# al_1S_charger.net
KiCad netlist of a schematic drawn in EAGLE
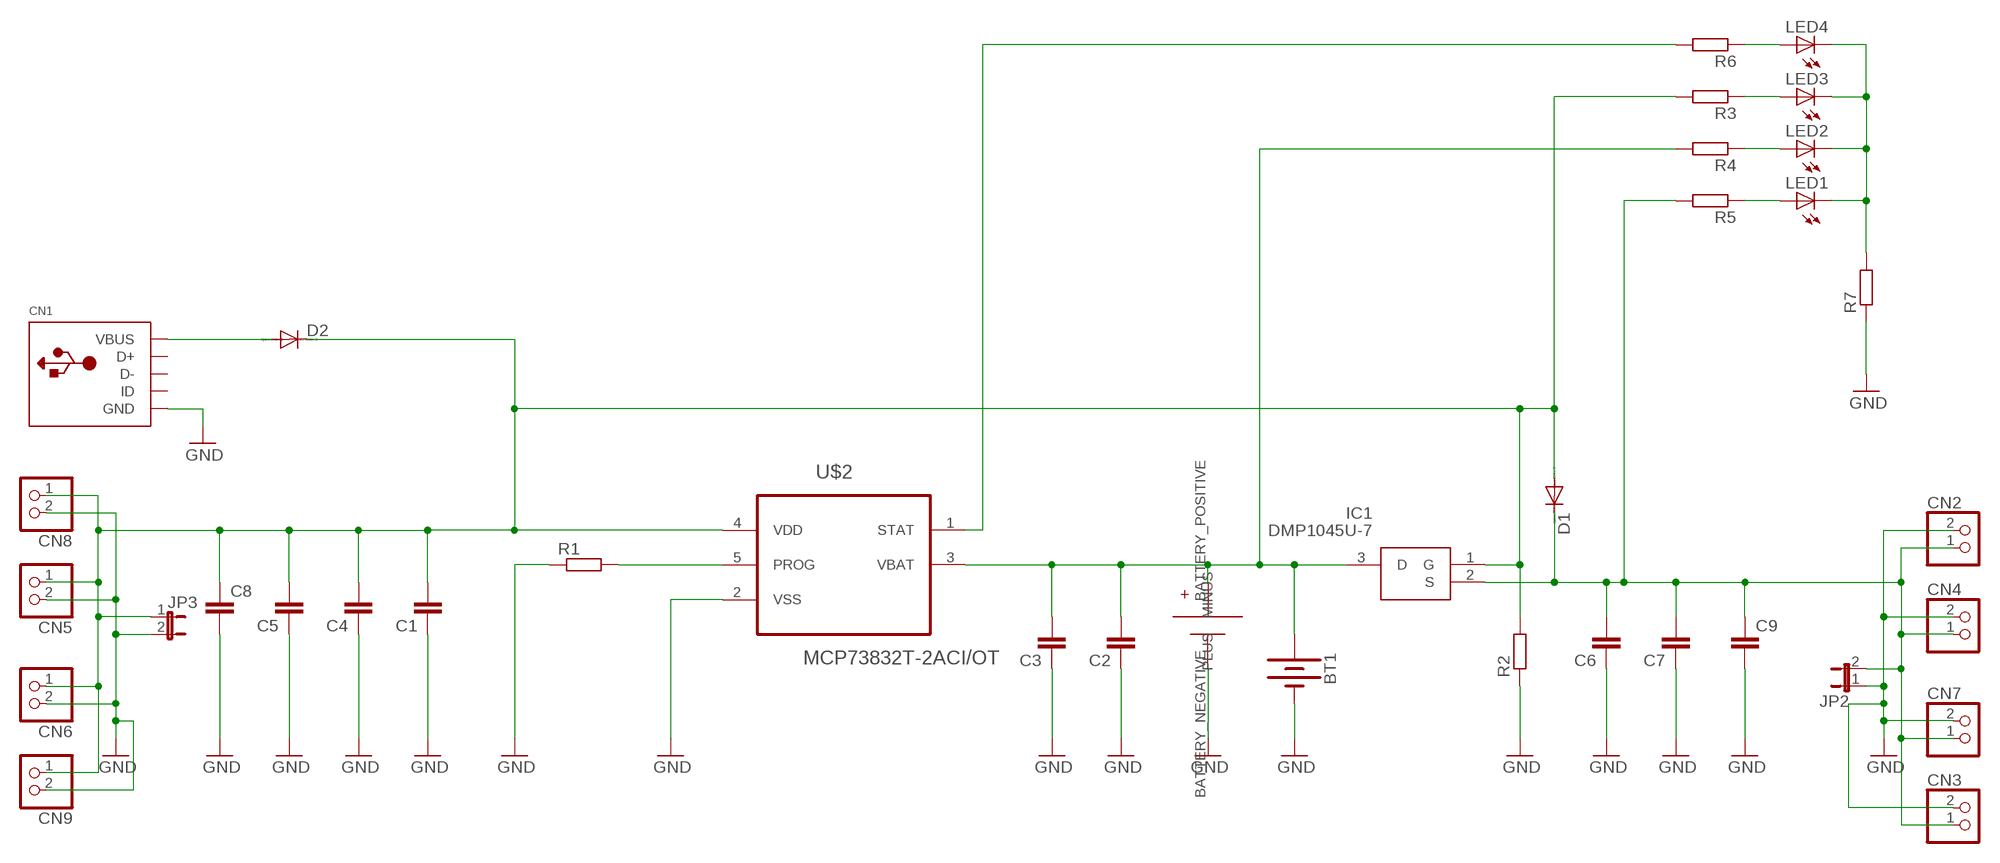
[diagram p0: schematic, sheet 1]

(export (version "E")
  (design (tool "Eeschema 10.0.6"))
  (components
    (comp (ref "BT1")
      (value "BATTERY-18650")
      (footprint "eagle-import:BATTERY_18650-HOLDER")
      (libsource (lib "eagle-import") (part "BATTERY-18650"))
    )
    (comp (ref "C1")
      (value "C-EUC0603")
      (footprint "eagle-import:C0603")
      (libsource (lib "eagle-import") (part "resistor_C-EUC0603"))
    )
    (comp (ref "C2")
      (value "C-EUC0603")
      (footprint "eagle-import:C0603")
      (libsource (lib "eagle-import") (part "resistor_C-EUC0603"))
    )
    (comp (ref "C3")
      (value "C-EUC0603")
      (footprint "eagle-import:C0603")
      (libsource (lib "eagle-import") (part "resistor_C-EUC0603"))
    )
    (comp (ref "C4")
      (value "C-EUC0603")
      (footprint "eagle-import:C0603")
      (libsource (lib "eagle-import") (part "resistor_C-EUC0603"))
    )
    (comp (ref "C5")
      (value "C-EUC0603")
      (footprint "eagle-import:C0603")
      (libsource (lib "eagle-import") (part "resistor_C-EUC0603"))
    )
    (comp (ref "C6")
      (value "C-EUC0603")
      (footprint "eagle-import:C0603")
      (libsource (lib "eagle-import") (part "resistor_C-EUC0603"))
    )
    (comp (ref "C7")
      (value "C-EUC0603")
      (footprint "eagle-import:C0603")
      (libsource (lib "eagle-import") (part "resistor_C-EUC0603"))
    )
    (comp (ref "C8")
      (value "C-EUC1210")
      (footprint "eagle-import:C1210")
      (libsource (lib "eagle-import") (part "C-EUC1210"))
    )
    (comp (ref "C9")
      (value "C-EUC1210")
      (footprint "eagle-import:C1210")
      (libsource (lib "eagle-import") (part "C-EUC1210"))
    )
    (comp (ref "CN1")
      (value "USBMINIB")
      (footprint "eagle-import:USB-MINIB")
      (libsource (lib "eagle-import") (part "USBMINIB"))
    )
    (comp (ref "CN2")
      (value "JST_2PIN-SMT-RA")
      (footprint "eagle-import:JST-PH-2-SMT-RA")
      (libsource (lib "eagle-import") (part "JST_2PIN-SMT-RA"))
    )
    (comp (ref "CN3")
      (value "JST_2PIN-SMT-RA")
      (footprint "eagle-import:JST-PH-2-SMT-RA")
      (libsource (lib "eagle-import") (part "JST_2PIN-SMT-RA"))
    )
    (comp (ref "CN4")
      (value "JST_2PIN-THM-RA")
      (footprint "eagle-import:JST-PH-2-THM-RA")
      (libsource (lib "eagle-import") (part "JST_2PIN-THM-RA"))
    )
    (comp (ref "CN5")
      (value "JST_2PIN-THM-RA")
      (footprint "eagle-import:JST-PH-2-THM-RA")
      (libsource (lib "eagle-import") (part "JST_2PIN-THM-RA"))
    )
    (comp (ref "CN6")
      (value "JST_2PIN-THM-RA")
      (footprint "eagle-import:JST-PH-2-THM-RA")
      (libsource (lib "eagle-import") (part "JST_2PIN-THM-RA"))
    )
    (comp (ref "CN7")
      (value "JST_2PIN-THM-RA")
      (footprint "eagle-import:JST-PH-2-THM-RA")
      (libsource (lib "eagle-import") (part "JST_2PIN-THM-RA"))
    )
    (comp (ref "CN8")
      (value "JST_2PIN-SMT-RA")
      (footprint "eagle-import:JST-PH-2-SMT-RA")
      (libsource (lib "eagle-import") (part "JST_2PIN-SMT-RA"))
    )
    (comp (ref "CN9")
      (value "JST_2PIN-SMT-RA")
      (footprint "eagle-import:JST-PH-2-SMT-RA")
      (libsource (lib "eagle-import") (part "JST_2PIN-SMT-RA"))
    )
    (comp (ref "D1")
      (value "DIODE-SMB")
      (footprint "eagle-import:SMB")
      (libsource (lib "eagle-import") (part "DIODE-SMB"))
    )
    (comp (ref "D2")
      (value "DIODE-SMB")
      (footprint "eagle-import:SMB")
      (libsource (lib "eagle-import") (part "DIODE-SMB"))
    )
    (comp (ref "IC1")
      (value "DMP1045U-7")
      (footprint "eagle-import:SOT96P240X100-3N")
      (fields (field (name "RS_PART_NUMBER") "8222605P"))
      (libsource (lib "eagle-import") (part "DMP1045U-7"))
    )
    (comp (ref "JP2")
      (value "JP1E")
      (footprint "eagle-import:JP1")
      (libsource (lib "eagle-import") (part "JP1E"))
    )
    (comp (ref "JP3")
      (value "JP1E")
      (footprint "eagle-import:JP1")
      (libsource (lib "eagle-import") (part "JP1E"))
    )
    (comp (ref "LED1")
      (value "LEDCHIP-LED0603")
      (footprint "eagle-import:CHIP-LED0603")
      (libsource (lib "eagle-import") (part "LEDCHIP-LED0603"))
    )
    (comp (ref "LED2")
      (value "LEDCHIP-LED0603")
      (footprint "eagle-import:CHIP-LED0603")
      (libsource (lib "eagle-import") (part "LEDCHIP-LED0603"))
    )
    (comp (ref "LED3")
      (value "LEDCHIP-LED0603")
      (footprint "eagle-import:CHIP-LED0603")
      (libsource (lib "eagle-import") (part "LEDCHIP-LED0603"))
    )
    (comp (ref "LED4")
      (value "LEDCHIP-LED0603")
      (footprint "eagle-import:CHIP-LED0603")
      (libsource (lib "eagle-import") (part "LEDCHIP-LED0603"))
    )
    (comp (ref "R1")
      (value "R-EU_R0603")
      (footprint "eagle-import:R0603")
      (libsource (lib "eagle-import") (part "R-EU_R0603"))
    )
    (comp (ref "R2")
      (value "R-EU_R0603")
      (footprint "eagle-import:R0603")
      (libsource (lib "eagle-import") (part "R-EU_R0603"))
    )
    (comp (ref "R3")
      (value "R-EU_R0603")
      (footprint "eagle-import:R0603")
      (libsource (lib "eagle-import") (part "R-EU_R0603"))
    )
    (comp (ref "R4")
      (value "R-EU_R0603")
      (footprint "eagle-import:R0603")
      (libsource (lib "eagle-import") (part "R-EU_R0603"))
    )
    (comp (ref "R5")
      (value "R-EU_R0603")
      (footprint "eagle-import:R0603")
      (libsource (lib "eagle-import") (part "R-EU_R0603"))
    )
    (comp (ref "R6")
      (value "R-EU_R0603")
      (footprint "eagle-import:R0603")
      (libsource (lib "eagle-import") (part "R-EU_R0603"))
    )
    (comp (ref "R7")
      (value "R-EU_R0603")
      (footprint "eagle-import:R0603")
      (libsource (lib "eagle-import") (part "R-EU_R0603"))
    )
    (comp (ref "U$1")
      (value "SMT18650_SMT18650")
      (footprint "eagle-import:SMT18650_18650SMT")
      (libsource (lib "eagle-import") (part "SMT18650_SMT18650"))
    )
    (comp (ref "U$2")
      (value "MCP73832T-2ACI/OT")
      (footprint "eagle-import:SOT95P280X145-5N")
      (libsource (lib "eagle-import") (part "MCP73832T-2ACI/OT"))
    )
  )
  (nets
    (net (code "1") (name "GND") (class "Default")
      (node (ref "BT1") (pin "GND@1") (pinfunction "-_GND@1") (pintype "power_in"))
      (node (ref "C1") (pin "1") (pinfunction "1_1") (pintype "passive"))
      (node (ref "C2") (pin "1") (pinfunction "1_1") (pintype "passive"))
      (node (ref "C3") (pin "1") (pinfunction "1_1") (pintype "passive"))
      (node (ref "C4") (pin "1") (pinfunction "1_1") (pintype "passive"))
      (node (ref "C5") (pin "1") (pinfunction "1_1") (pintype "passive"))
      (node (ref "C6") (pin "1") (pinfunction "1_1") (pintype "passive"))
      (node (ref "C7") (pin "1") (pinfunction "1_1") (pintype "passive"))
      (node (ref "C8") (pin "2") (pinfunction "2_2") (pintype "passive"))
      (node (ref "C9") (pin "2") (pinfunction "2_2") (pintype "passive"))
      (node (ref "CN1") (pin "GND") (pinfunction "GND_GND") (pintype "power_in"))
      (node (ref "CN2") (pin "2") (pinfunction "1_2") (pintype "passive"))
      (node (ref "CN3") (pin "2") (pinfunction "1_2") (pintype "passive"))
      (node (ref "CN4") (pin "2") (pinfunction "1_2") (pintype "passive"))
      (node (ref "CN5") (pin "2") (pinfunction "1_2") (pintype "passive"))
      (node (ref "CN6") (pin "2") (pinfunction "1_2") (pintype "passive"))
      (node (ref "CN7") (pin "2") (pinfunction "1_2") (pintype "passive"))
      (node (ref "CN8") (pin "2") (pinfunction "1_2") (pintype "passive"))
      (node (ref "CN9") (pin "2") (pinfunction "1_2") (pintype "passive"))
      (node (ref "JP2") (pin "1") (pinfunction "1_1") (pintype "passive"))
      (node (ref "JP3") (pin "2") (pinfunction "2_2") (pintype "passive"))
      (node (ref "R1") (pin "1") (pinfunction "1_1") (pintype "passive"))
      (node (ref "R2") (pin "1") (pinfunction "1_1") (pintype "passive"))
      (node (ref "R7") (pin "1") (pinfunction "1_1") (pintype "passive"))
      (node (ref "U$1") (pin "BATTERY_NEGATIVE") (pinfunction "MINUS_BATTERY_NEGATIVE") (pintype "bidirectional"))
      (node (ref "U$2") (pin "2") (pinfunction "VSS_2") (pintype "power_in"))
    )
    (net (code "2") (name "Net-(BT1-+)") (class "Default")
      (node (ref "BT1") (pin "PWR@1") (pinfunction "+_PWR@1") (pintype "power_in"))
      (node (ref "C2") (pin "2") (pinfunction "2_2") (pintype "passive"))
      (node (ref "C3") (pin "2") (pinfunction "2_2") (pintype "passive"))
      (node (ref "IC1") (pin "3") (pinfunction "D_3") (pintype "bidirectional"))
      (node (ref "R4") (pin "2") (pinfunction "2_2") (pintype "passive"))
      (node (ref "U$1") (pin "BATTERY_POSITIVE") (pinfunction "PLUS_BATTERY_POSITIVE") (pintype "bidirectional"))
      (node (ref "U$2") (pin "3") (pinfunction "VBAT_3") (pintype "output"))
    )
    (net (code "3") (name "Net-(CN1-PadVBUS)") (class "Default")
      (node (ref "CN1") (pin "VBUS") (pinfunction "VBUS_VBUS") (pintype "power_in"))
      (node (ref "D2") (pin "A") (pinfunction "A_A") (pintype "passive"))
    )
    (net (code "4") (name "Net-(CN2-2)") (class "Default")
      (node (ref "C6") (pin "2") (pinfunction "2_2") (pintype "passive"))
      (node (ref "C7") (pin "2") (pinfunction "2_2") (pintype "passive"))
      (node (ref "C9") (pin "1") (pinfunction "1_1") (pintype "passive"))
      (node (ref "CN2") (pin "1") (pinfunction "2_1") (pintype "passive"))
      (node (ref "CN3") (pin "1") (pinfunction "2_1") (pintype "passive"))
      (node (ref "CN4") (pin "1") (pinfunction "2_1") (pintype "passive"))
      (node (ref "CN7") (pin "1") (pinfunction "2_1") (pintype "passive"))
      (node (ref "D1") (pin "C") (pinfunction "C_C") (pintype "passive"))
      (node (ref "IC1") (pin "2") (pinfunction "S_2") (pintype "bidirectional"))
      (node (ref "JP2") (pin "2") (pinfunction "2_2") (pintype "passive"))
      (node (ref "R5") (pin "2") (pinfunction "2_2") (pintype "passive"))
    )
    (net (code "5") (name "Net-(CN5-2)") (class "Default")
      (node (ref "C1") (pin "2") (pinfunction "2_2") (pintype "passive"))
      (node (ref "C4") (pin "2") (pinfunction "2_2") (pintype "passive"))
      (node (ref "C5") (pin "2") (pinfunction "2_2") (pintype "passive"))
      (node (ref "C8") (pin "1") (pinfunction "1_1") (pintype "passive"))
      (node (ref "CN5") (pin "1") (pinfunction "2_1") (pintype "passive"))
      (node (ref "CN6") (pin "1") (pinfunction "2_1") (pintype "passive"))
      (node (ref "CN8") (pin "1") (pinfunction "2_1") (pintype "passive"))
      (node (ref "CN9") (pin "1") (pinfunction "2_1") (pintype "passive"))
      (node (ref "D1") (pin "A") (pinfunction "A_A") (pintype "passive"))
      (node (ref "D2") (pin "C") (pinfunction "C_C") (pintype "passive"))
      (node (ref "IC1") (pin "1") (pinfunction "G_1") (pintype "bidirectional"))
      (node (ref "JP3") (pin "1") (pinfunction "1_1") (pintype "passive"))
      (node (ref "R2") (pin "2") (pinfunction "2_2") (pintype "passive"))
      (node (ref "R3") (pin "2") (pinfunction "2_2") (pintype "passive"))
      (node (ref "U$2") (pin "4") (pinfunction "VDD_4") (pintype "power_in"))
    )
    (net (code "6") (name "Net-(LED1-PadA)") (class "Default")
      (node (ref "LED1") (pin "A") (pinfunction "A_A") (pintype "passive"))
      (node (ref "R5") (pin "1") (pinfunction "1_1") (pintype "passive"))
    )
    (net (code "7") (name "Net-(LED1-PadC)") (class "Default")
      (node (ref "LED1") (pin "C") (pinfunction "C_C") (pintype "passive"))
      (node (ref "LED2") (pin "C") (pinfunction "C_C") (pintype "passive"))
      (node (ref "LED3") (pin "C") (pinfunction "C_C") (pintype "passive"))
      (node (ref "LED4") (pin "C") (pinfunction "C_C") (pintype "passive"))
      (node (ref "R7") (pin "2") (pinfunction "2_2") (pintype "passive"))
    )
    (net (code "8") (name "Net-(LED2-PadA)") (class "Default")
      (node (ref "LED2") (pin "A") (pinfunction "A_A") (pintype "passive"))
      (node (ref "R4") (pin "1") (pinfunction "1_1") (pintype "passive"))
    )
    (net (code "9") (name "Net-(LED3-PadA)") (class "Default")
      (node (ref "LED3") (pin "A") (pinfunction "A_A") (pintype "passive"))
      (node (ref "R3") (pin "1") (pinfunction "1_1") (pintype "passive"))
    )
    (net (code "10") (name "Net-(LED4-PadA)") (class "Default")
      (node (ref "LED4") (pin "A") (pinfunction "A_A") (pintype "passive"))
      (node (ref "R6") (pin "1") (pinfunction "1_1") (pintype "passive"))
    )
    (net (code "11") (name "Net-(U$2-PROG)") (class "Default")
      (node (ref "R1") (pin "2") (pinfunction "2_2") (pintype "passive"))
      (node (ref "U$2") (pin "5") (pinfunction "PROG_5") (pintype "input"))
    )
    (net (code "12") (name "Net-(U$2-STAT)") (class "Default")
      (node (ref "R6") (pin "2") (pinfunction "2_2") (pintype "passive"))
      (node (ref "U$2") (pin "1") (pinfunction "STAT_1") (pintype "output"))
    )
    (net (code "13") (name "unconnected-(CN1-PadD+)") (class "Default")
      (node (ref "CN1") (pin "D+") (pinfunction "D+_D+") (pintype "bidirectional"))
    )
    (net (code "14") (name "unconnected-(CN1-PadD-)") (class "Default")
      (node (ref "CN1") (pin "D-") (pinfunction "D-_D-") (pintype "bidirectional"))
    )
    (net (code "15") (name "unconnected-(CN1-PadID)") (class "Default")
      (node (ref "CN1") (pin "ID") (pinfunction "ID_ID") (pintype "bidirectional"))
    )
  )
)
